# axiom_beta_interface_dummy.net
KiCad netlist of a schematic drawn in EAGLE
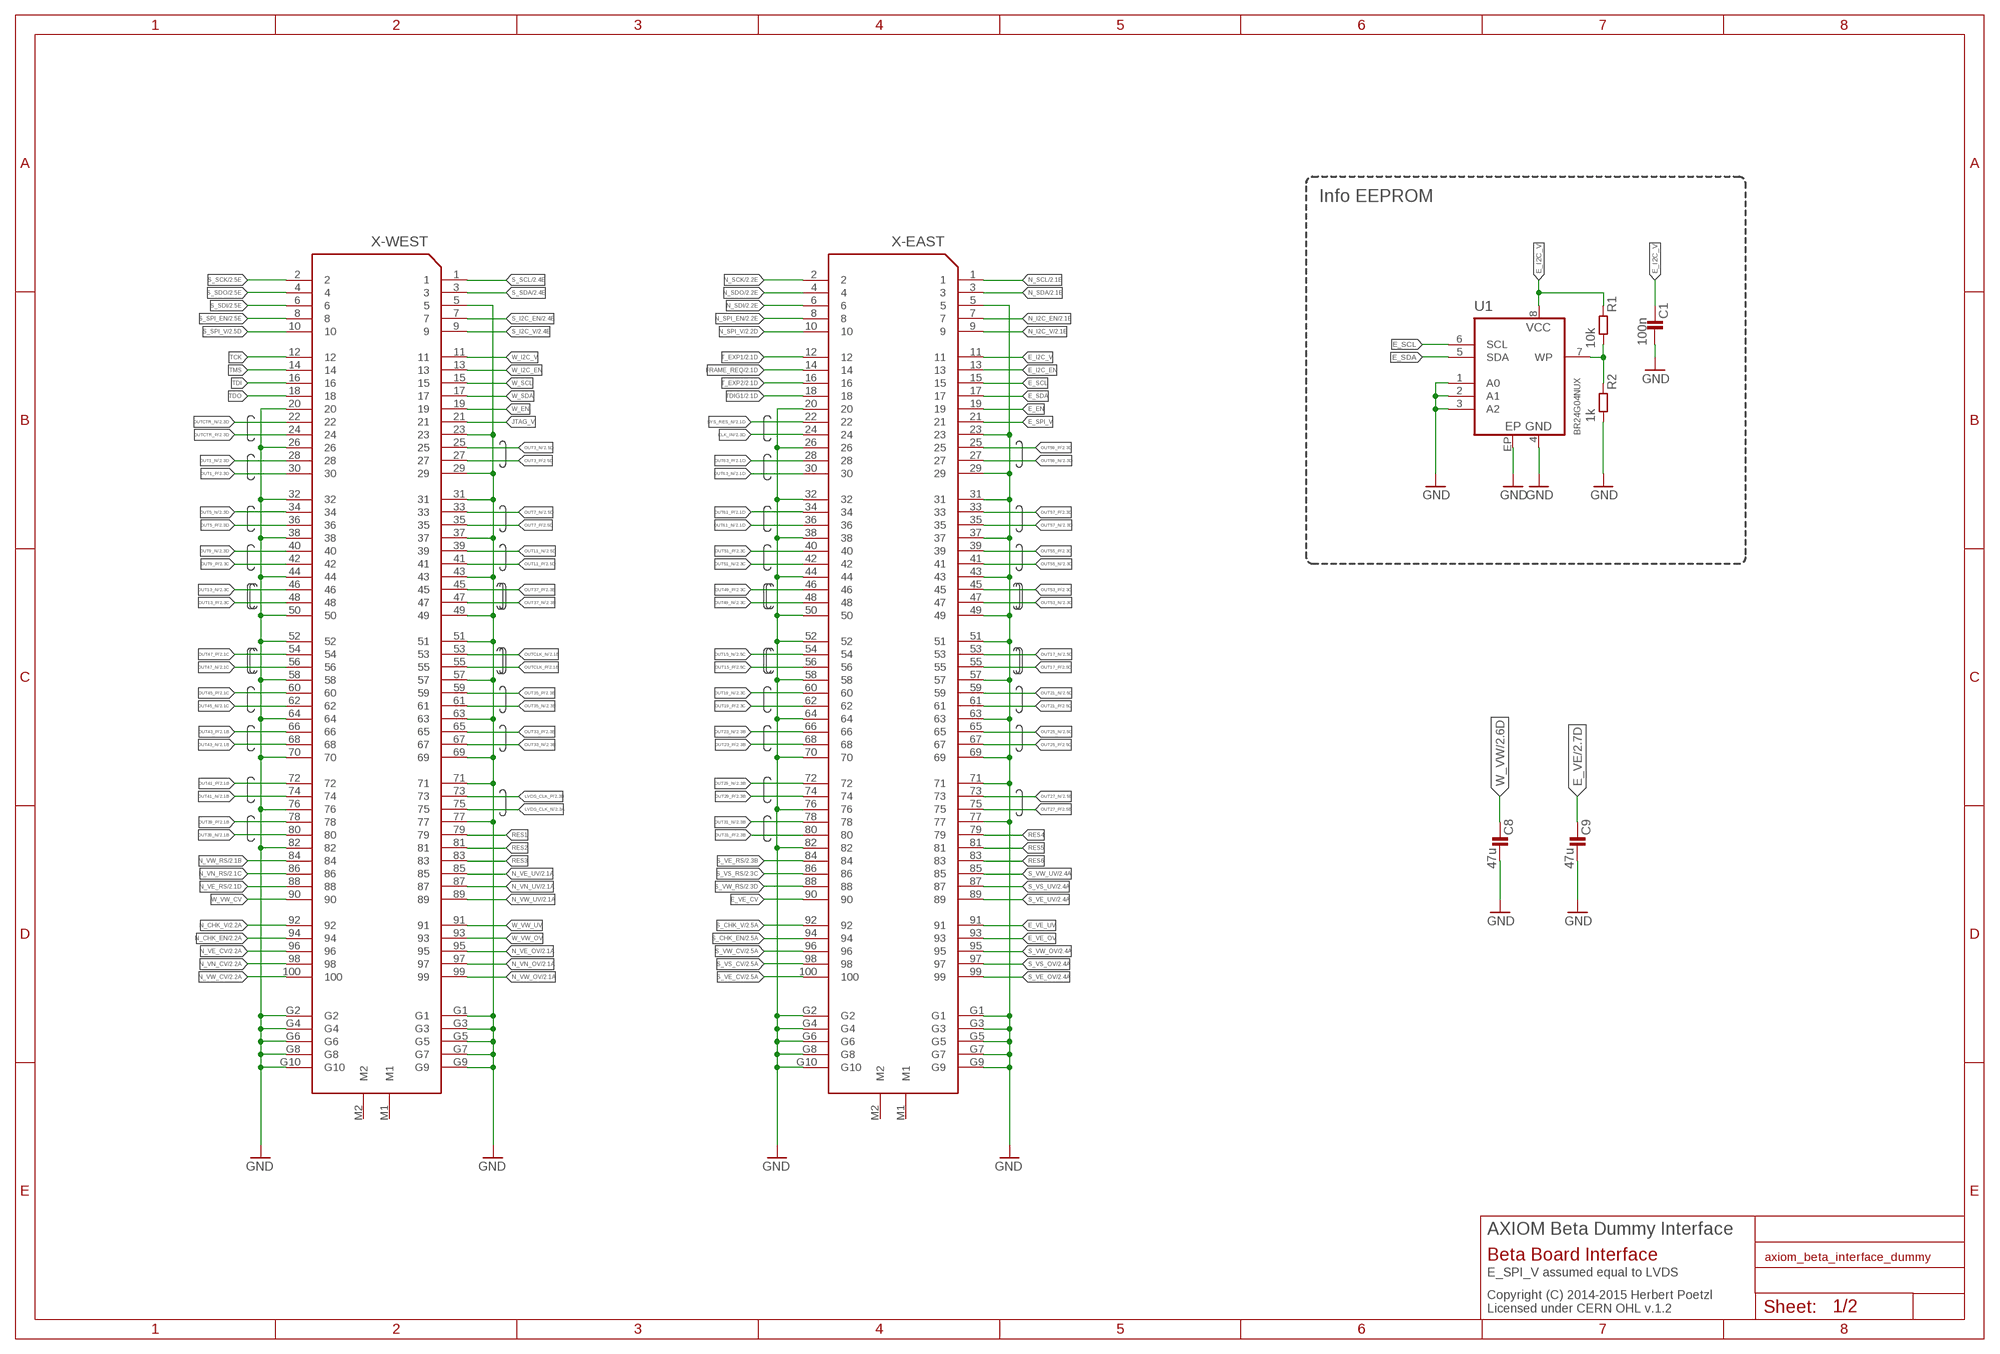
[diagram p0: schematic, sheet 1]
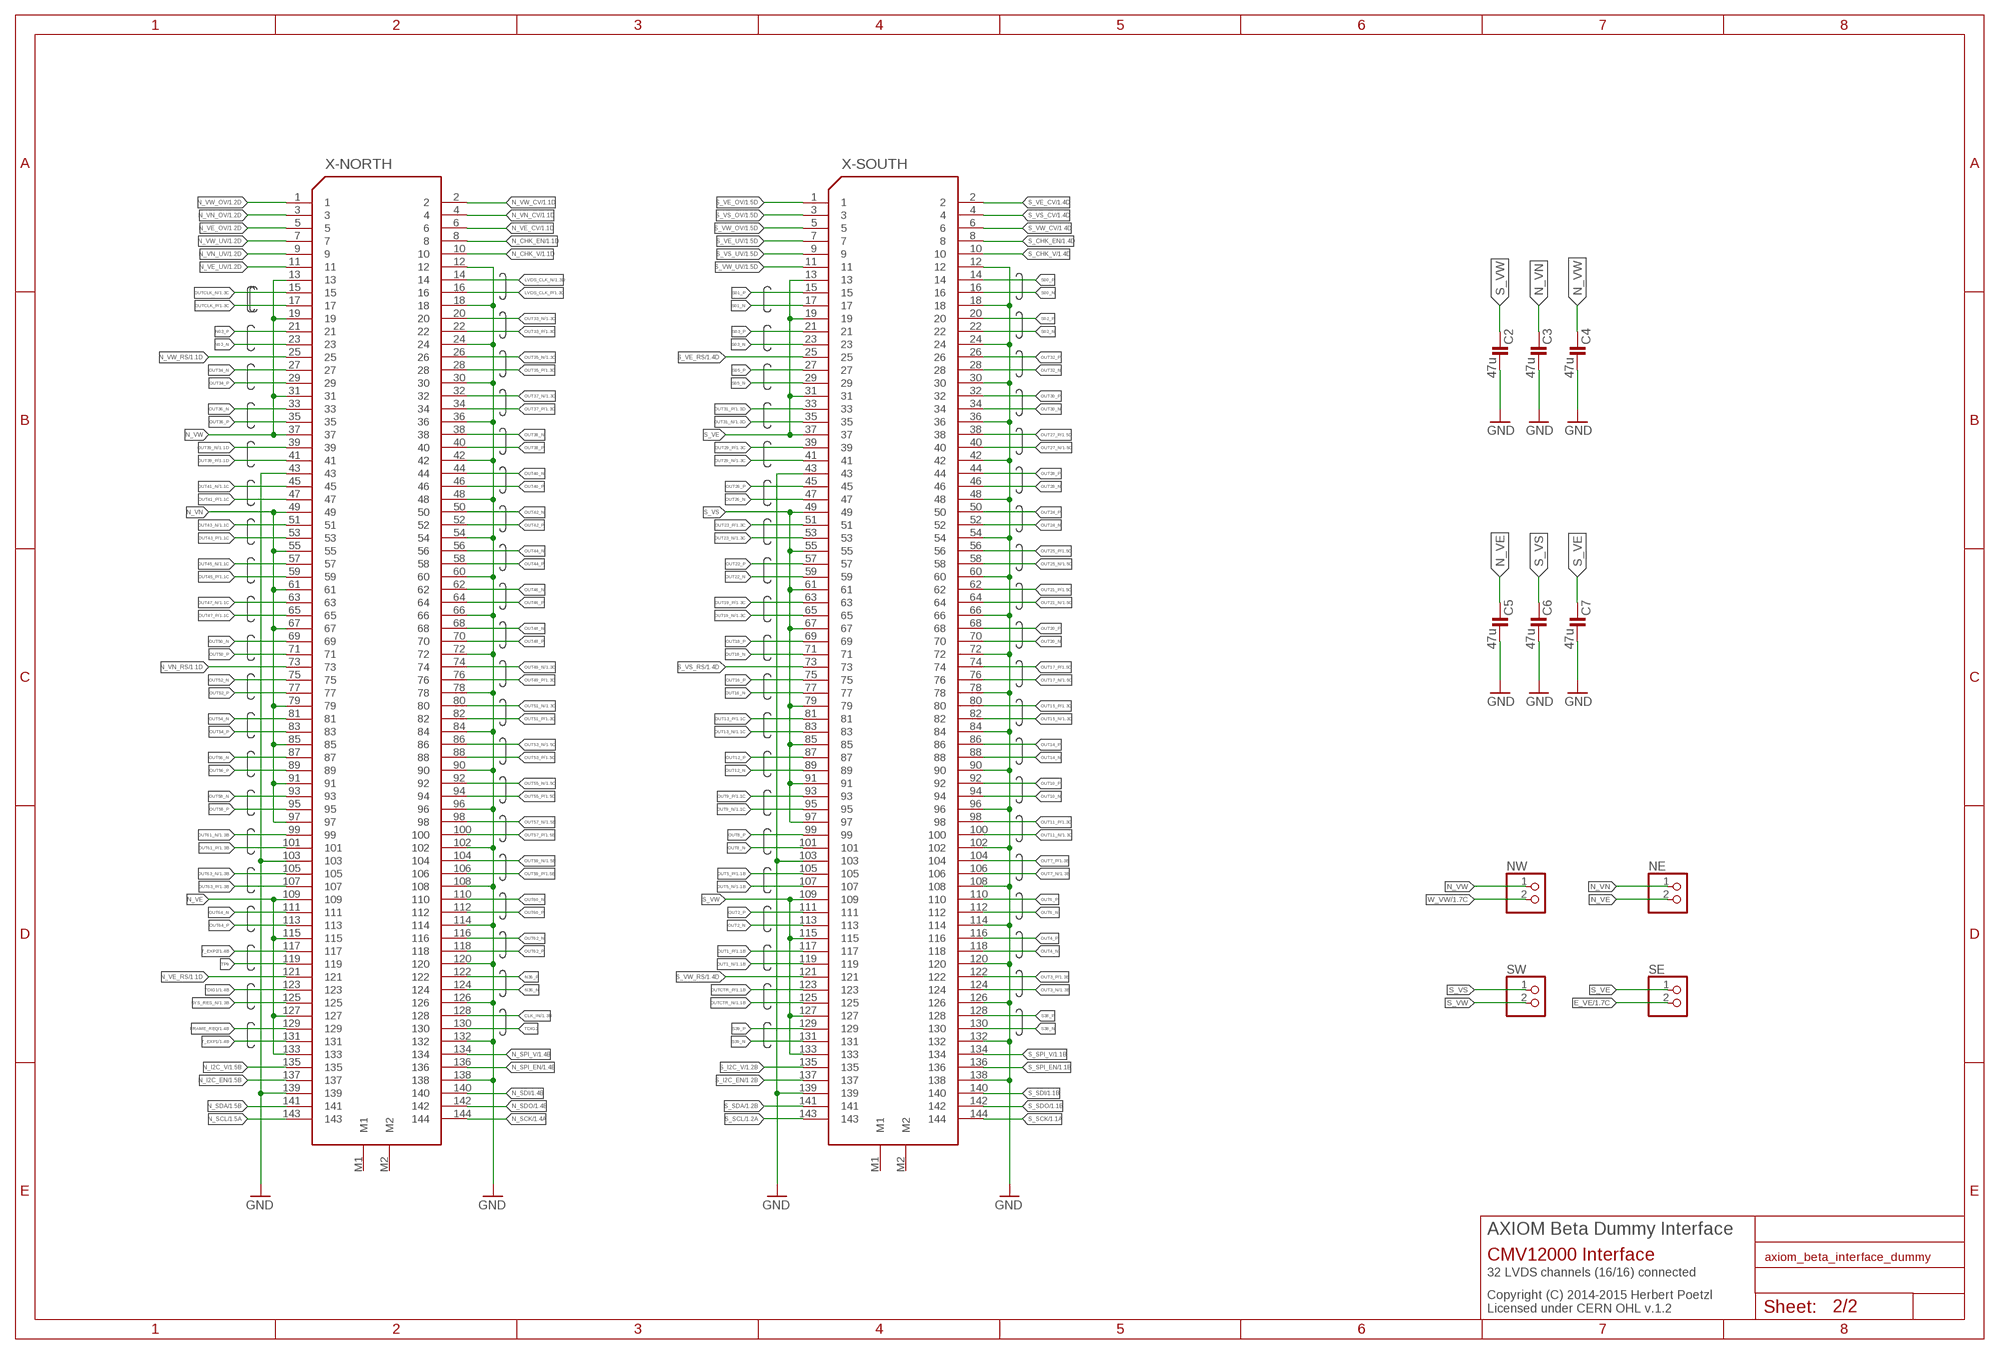
[diagram p1: schematic, sheet 2]

(export (version "E")
  (design (tool "Eeschema 10.0.6"))
  (components
    (comp (ref "C1")
      (value "100n")
      (footprint "eagle-import:0402-B")
      (libsource (lib "eagle-import") (part "C0402-B"))
    )
    (comp (ref "C8")
      (value "47u")
      (footprint "eagle-import:0805-B")
      (libsource (lib "eagle-import") (part "C0805-B"))
    )
    (comp (ref "C9")
      (value "47u")
      (footprint "eagle-import:0805-B")
      (libsource (lib "eagle-import") (part "C0805-B"))
    )
    (comp (ref "R1")
      (value "10k")
      (footprint "eagle-import:0402-B")
      (libsource (lib "eagle-import") (part "R0402-B"))
    )
    (comp (ref "R2")
      (value "1k")
      (footprint "eagle-import:0402-B")
      (libsource (lib "eagle-import") (part "R0402-B"))
    )
    (comp (ref "U1")
      (value "BR24G04NUX")
      (footprint "eagle-import:DFN200X300X100-9N")
      (libsource (lib "eagle-import") (part "BR24G04NUX"))
    )
    (comp (ref "X-EAST")
      (value "FX10-100/10P")
      (footprint "eagle-import:FX10A-100P_10")
      (libsource (lib "eagle-import") (part "FX10-100/10P"))
    )
    (comp (ref "X-WEST")
      (value "FX10-100/10P")
      (footprint "eagle-import:FX10A-100P_10")
      (libsource (lib "eagle-import") (part "FX10-100/10P"))
    )
    (comp (ref "C2")
      (value "47u")
      (footprint "eagle-import:0805-B")
      (libsource (lib "eagle-import") (part "C0805-B"))
    )
    (comp (ref "C3")
      (value "47u")
      (footprint "eagle-import:0805-B")
      (libsource (lib "eagle-import") (part "C0805-B"))
    )
    (comp (ref "C4")
      (value "47u")
      (footprint "eagle-import:0805-B")
      (libsource (lib "eagle-import") (part "C0805-B"))
    )
    (comp (ref "C5")
      (value "47u")
      (footprint "eagle-import:0805-B")
      (libsource (lib "eagle-import") (part "C0805-B"))
    )
    (comp (ref "C6")
      (value "47u")
      (footprint "eagle-import:0805-B")
      (libsource (lib "eagle-import") (part "C0805-B"))
    )
    (comp (ref "C7")
      (value "47u")
      (footprint "eagle-import:0805-B")
      (libsource (lib "eagle-import") (part "C0805-B"))
    )
    (comp (ref "NE")
      (value "PINHD-1X02_2.54")
      (footprint "eagle-import:1X02")
      (libsource (lib "eagle-import") (part "PINHD-1X02_2.54"))
    )
    (comp (ref "NW")
      (value "PINHD-1X02_2.54")
      (footprint "eagle-import:1X02")
      (libsource (lib "eagle-import") (part "PINHD-1X02_2.54"))
    )
    (comp (ref "SE")
      (value "PINHD-1X02_2.54")
      (footprint "eagle-import:1X02")
      (libsource (lib "eagle-import") (part "PINHD-1X02_2.54"))
    )
    (comp (ref "SW")
      (value "PINHD-1X02_2.54")
      (footprint "eagle-import:1X02")
      (libsource (lib "eagle-import") (part "PINHD-1X02_2.54"))
    )
    (comp (ref "X-NORTH")
      (value "FX10-144S")
      (footprint "eagle-import:FX10A-144S")
      (libsource (lib "eagle-import") (part "FX10-144S"))
    )
    (comp (ref "X-SOUTH")
      (value "FX10-144S")
      (footprint "eagle-import:FX10A-144S")
      (libsource (lib "eagle-import") (part "FX10-144S"))
    )
  )
  (nets
    (net (code "1") (name "CLK_IN") (class "Default")
      (node (ref "X-EAST") (pin "24") (pinfunction "24_24") (pintype "bidirectional"))
      (node (ref "X-NORTH") (pin "128") (pinfunction "128_128") (pintype "bidirectional"))
    )
    (net (code "2") (name "E_EN") (class "Default")
      (node (ref "X-EAST") (pin "19") (pinfunction "19_19") (pintype "bidirectional"))
    )
    (net (code "3") (name "E_I2C_EN") (class "Default")
      (node (ref "X-EAST") (pin "13") (pinfunction "13_13") (pintype "bidirectional"))
    )
    (net (code "4") (name "E_I2C_V") (class "Default")
      (node (ref "C1") (pin "1") (pinfunction "1_1") (pintype "passive"))
      (node (ref "R1") (pin "1") (pinfunction "1_1") (pintype "passive"))
      (node (ref "U1") (pin "8") (pinfunction "VCC_8") (pintype "power_in"))
      (node (ref "X-EAST") (pin "11") (pinfunction "11_11") (pintype "bidirectional"))
    )
    (net (code "5") (name "E_SCL") (class "Default")
      (node (ref "U1") (pin "6") (pinfunction "SCL_6") (pintype "input"))
      (node (ref "X-EAST") (pin "15") (pinfunction "15_15") (pintype "bidirectional"))
    )
    (net (code "6") (name "E_SDA") (class "Default")
      (node (ref "U1") (pin "5") (pinfunction "SDA_5") (pintype "bidirectional"))
      (node (ref "X-EAST") (pin "17") (pinfunction "17_17") (pintype "bidirectional"))
    )
    (net (code "7") (name "E_SPI_V") (class "Default")
      (node (ref "X-EAST") (pin "21") (pinfunction "21_21") (pintype "bidirectional"))
    )
    (net (code "8") (name "E_VE") (class "Default")
      (node (ref "C9") (pin "1") (pinfunction "1_1") (pintype "passive"))
      (node (ref "SE") (pin "2") (pinfunction "2_2") (pintype "passive"))
    )
    (net (code "9") (name "E_VE_CV") (class "Default")
      (node (ref "X-EAST") (pin "90") (pinfunction "90_90") (pintype "bidirectional"))
    )
    (net (code "10") (name "E_VE_OV") (class "Default")
      (node (ref "X-EAST") (pin "93") (pinfunction "93_93") (pintype "bidirectional"))
    )
    (net (code "11") (name "E_VE_UV") (class "Default")
      (node (ref "X-EAST") (pin "91") (pinfunction "91_91") (pintype "bidirectional"))
    )
    (net (code "12") (name "FRAME_REQ") (class "Default")
      (node (ref "X-EAST") (pin "14") (pinfunction "14_14") (pintype "bidirectional"))
      (node (ref "X-NORTH") (pin "129") (pinfunction "129_129") (pintype "bidirectional"))
    )
    (net (code "13") (name "GND") (class "Default")
      (node (ref "C1") (pin "2") (pinfunction "2_2") (pintype "passive"))
      (node (ref "C2") (pin "2") (pinfunction "2_2") (pintype "passive"))
      (node (ref "C3") (pin "2") (pinfunction "2_2") (pintype "passive"))
      (node (ref "C4") (pin "2") (pinfunction "2_2") (pintype "passive"))
      (node (ref "C5") (pin "2") (pinfunction "2_2") (pintype "passive"))
      (node (ref "C6") (pin "2") (pinfunction "2_2") (pintype "passive"))
      (node (ref "C7") (pin "2") (pinfunction "2_2") (pintype "passive"))
      (node (ref "C8") (pin "2") (pinfunction "2_2") (pintype "passive"))
      (node (ref "C9") (pin "2") (pinfunction "2_2") (pintype "passive"))
      (node (ref "R2") (pin "2") (pinfunction "2_2") (pintype "passive"))
      (node (ref "U1") (pin "1") (pinfunction "A0_1") (pintype "input"))
      (node (ref "U1") (pin "2") (pinfunction "A1_2") (pintype "input"))
      (node (ref "U1") (pin "3") (pinfunction "A2_3") (pintype "input"))
      (node (ref "U1") (pin "4") (pinfunction "GND_4") (pintype "passive"))
      (node (ref "U1") (pin "EP") (pinfunction "EP_EP") (pintype "passive"))
      (node (ref "X-EAST") (pin "20") (pinfunction "20_20") (pintype "bidirectional"))
      (node (ref "X-EAST") (pin "23") (pinfunction "23_23") (pintype "bidirectional"))
      (node (ref "X-EAST") (pin "26") (pinfunction "26_26") (pintype "bidirectional"))
      (node (ref "X-EAST") (pin "29") (pinfunction "29_29") (pintype "bidirectional"))
      (node (ref "X-EAST") (pin "31") (pinfunction "31_31") (pintype "bidirectional"))
      (node (ref "X-EAST") (pin "32") (pinfunction "32_32") (pintype "bidirectional"))
      (node (ref "X-EAST") (pin "37") (pinfunction "37_37") (pintype "bidirectional"))
      (node (ref "X-EAST") (pin "38") (pinfunction "38_38") (pintype "bidirectional"))
      (node (ref "X-EAST") (pin "43") (pinfunction "43_43") (pintype "bidirectional"))
      (node (ref "X-EAST") (pin "44") (pinfunction "44_44") (pintype "bidirectional"))
      (node (ref "X-EAST") (pin "49") (pinfunction "49_49") (pintype "bidirectional"))
      (node (ref "X-EAST") (pin "5") (pinfunction "5_5") (pintype "bidirectional"))
      (node (ref "X-EAST") (pin "50") (pinfunction "50_50") (pintype "bidirectional"))
      (node (ref "X-EAST") (pin "51") (pinfunction "51_51") (pintype "bidirectional"))
      (node (ref "X-EAST") (pin "52") (pinfunction "52_52") (pintype "bidirectional"))
      (node (ref "X-EAST") (pin "57") (pinfunction "57_57") (pintype "bidirectional"))
      (node (ref "X-EAST") (pin "58") (pinfunction "58_58") (pintype "bidirectional"))
      (node (ref "X-EAST") (pin "63") (pinfunction "63_63") (pintype "bidirectional"))
      (node (ref "X-EAST") (pin "64") (pinfunction "64_64") (pintype "bidirectional"))
      (node (ref "X-EAST") (pin "69") (pinfunction "69_69") (pintype "bidirectional"))
      (node (ref "X-EAST") (pin "70") (pinfunction "70_70") (pintype "bidirectional"))
      (node (ref "X-EAST") (pin "71") (pinfunction "71_71") (pintype "bidirectional"))
      (node (ref "X-EAST") (pin "76") (pinfunction "76_76") (pintype "bidirectional"))
      (node (ref "X-EAST") (pin "77") (pinfunction "77_77") (pintype "bidirectional"))
      (node (ref "X-EAST") (pin "82") (pinfunction "82_82") (pintype "bidirectional"))
      (node (ref "X-EAST") (pin "G1") (pinfunction "G1_G1") (pintype "bidirectional"))
      (node (ref "X-EAST") (pin "G10") (pinfunction "G10_G10") (pintype "bidirectional"))
      (node (ref "X-EAST") (pin "G2") (pinfunction "G2_G2") (pintype "bidirectional"))
      (node (ref "X-EAST") (pin "G3") (pinfunction "G3_G3") (pintype "bidirectional"))
      (node (ref "X-EAST") (pin "G4") (pinfunction "G4_G4") (pintype "bidirectional"))
      (node (ref "X-EAST") (pin "G5") (pinfunction "G5_G5") (pintype "bidirectional"))
      (node (ref "X-EAST") (pin "G6") (pinfunction "G6_G6") (pintype "bidirectional"))
      (node (ref "X-EAST") (pin "G7") (pinfunction "G7_G7") (pintype "bidirectional"))
      (node (ref "X-EAST") (pin "G8") (pinfunction "G8_G8") (pintype "bidirectional"))
      (node (ref "X-EAST") (pin "G9") (pinfunction "G9_G9") (pintype "bidirectional"))
      (node (ref "X-NORTH") (pin "102") (pinfunction "102_102") (pintype "bidirectional"))
      (node (ref "X-NORTH") (pin "103") (pinfunction "103_103") (pintype "bidirectional"))
      (node (ref "X-NORTH") (pin "108") (pinfunction "108_108") (pintype "bidirectional"))
      (node (ref "X-NORTH") (pin "114") (pinfunction "114_114") (pintype "bidirectional"))
      (node (ref "X-NORTH") (pin "12") (pinfunction "12_12") (pintype "bidirectional"))
      (node (ref "X-NORTH") (pin "120") (pinfunction "120_120") (pintype "bidirectional"))
      (node (ref "X-NORTH") (pin "126") (pinfunction "126_126") (pintype "bidirectional"))
      (node (ref "X-NORTH") (pin "132") (pinfunction "132_132") (pintype "bidirectional"))
      (node (ref "X-NORTH") (pin "138") (pinfunction "138_138") (pintype "bidirectional"))
      (node (ref "X-NORTH") (pin "139") (pinfunction "139_139") (pintype "bidirectional"))
      (node (ref "X-NORTH") (pin "18") (pinfunction "18_18") (pintype "bidirectional"))
      (node (ref "X-NORTH") (pin "24") (pinfunction "24_24") (pintype "bidirectional"))
      (node (ref "X-NORTH") (pin "30") (pinfunction "30_30") (pintype "bidirectional"))
      (node (ref "X-NORTH") (pin "36") (pinfunction "36_36") (pintype "bidirectional"))
      (node (ref "X-NORTH") (pin "42") (pinfunction "42_42") (pintype "bidirectional"))
      (node (ref "X-NORTH") (pin "43") (pinfunction "43_43") (pintype "bidirectional"))
      (node (ref "X-NORTH") (pin "48") (pinfunction "48_48") (pintype "bidirectional"))
      (node (ref "X-NORTH") (pin "54") (pinfunction "54_54") (pintype "bidirectional"))
      (node (ref "X-NORTH") (pin "60") (pinfunction "60_60") (pintype "bidirectional"))
      (node (ref "X-NORTH") (pin "66") (pinfunction "66_66") (pintype "bidirectional"))
      (node (ref "X-NORTH") (pin "72") (pinfunction "72_72") (pintype "bidirectional"))
      (node (ref "X-NORTH") (pin "78") (pinfunction "78_78") (pintype "bidirectional"))
      (node (ref "X-NORTH") (pin "84") (pinfunction "84_84") (pintype "bidirectional"))
      (node (ref "X-NORTH") (pin "90") (pinfunction "90_90") (pintype "bidirectional"))
      (node (ref "X-NORTH") (pin "96") (pinfunction "96_96") (pintype "bidirectional"))
      (node (ref "X-SOUTH") (pin "102") (pinfunction "102_102") (pintype "bidirectional"))
      (node (ref "X-SOUTH") (pin "103") (pinfunction "103_103") (pintype "bidirectional"))
      (node (ref "X-SOUTH") (pin "108") (pinfunction "108_108") (pintype "bidirectional"))
      (node (ref "X-SOUTH") (pin "114") (pinfunction "114_114") (pintype "bidirectional"))
      (node (ref "X-SOUTH") (pin "12") (pinfunction "12_12") (pintype "bidirectional"))
      (node (ref "X-SOUTH") (pin "120") (pinfunction "120_120") (pintype "bidirectional"))
      (node (ref "X-SOUTH") (pin "126") (pinfunction "126_126") (pintype "bidirectional"))
      (node (ref "X-SOUTH") (pin "132") (pinfunction "132_132") (pintype "bidirectional"))
      (node (ref "X-SOUTH") (pin "138") (pinfunction "138_138") (pintype "bidirectional"))
      (node (ref "X-SOUTH") (pin "139") (pinfunction "139_139") (pintype "bidirectional"))
      (node (ref "X-SOUTH") (pin "18") (pinfunction "18_18") (pintype "bidirectional"))
      (node (ref "X-SOUTH") (pin "24") (pinfunction "24_24") (pintype "bidirectional"))
      (node (ref "X-SOUTH") (pin "30") (pinfunction "30_30") (pintype "bidirectional"))
      (node (ref "X-SOUTH") (pin "36") (pinfunction "36_36") (pintype "bidirectional"))
      (node (ref "X-SOUTH") (pin "42") (pinfunction "42_42") (pintype "bidirectional"))
      (node (ref "X-SOUTH") (pin "43") (pinfunction "43_43") (pintype "bidirectional"))
      (node (ref "X-SOUTH") (pin "48") (pinfunction "48_48") (pintype "bidirectional"))
      (node (ref "X-SOUTH") (pin "54") (pinfunction "54_54") (pintype "bidirectional"))
      (node (ref "X-SOUTH") (pin "60") (pinfunction "60_60") (pintype "bidirectional"))
      (node (ref "X-SOUTH") (pin "66") (pinfunction "66_66") (pintype "bidirectional"))
      (node (ref "X-SOUTH") (pin "72") (pinfunction "72_72") (pintype "bidirectional"))
      (node (ref "X-SOUTH") (pin "78") (pinfunction "78_78") (pintype "bidirectional"))
      (node (ref "X-SOUTH") (pin "84") (pinfunction "84_84") (pintype "bidirectional"))
      (node (ref "X-SOUTH") (pin "90") (pinfunction "90_90") (pintype "bidirectional"))
      (node (ref "X-SOUTH") (pin "96") (pinfunction "96_96") (pintype "bidirectional"))
      (node (ref "X-WEST") (pin "20") (pinfunction "20_20") (pintype "bidirectional"))
      (node (ref "X-WEST") (pin "23") (pinfunction "23_23") (pintype "bidirectional"))
      (node (ref "X-WEST") (pin "26") (pinfunction "26_26") (pintype "bidirectional"))
      (node (ref "X-WEST") (pin "29") (pinfunction "29_29") (pintype "bidirectional"))
      (node (ref "X-WEST") (pin "31") (pinfunction "31_31") (pintype "bidirectional"))
      (node (ref "X-WEST") (pin "32") (pinfunction "32_32") (pintype "bidirectional"))
      (node (ref "X-WEST") (pin "37") (pinfunction "37_37") (pintype "bidirectional"))
      (node (ref "X-WEST") (pin "38") (pinfunction "38_38") (pintype "bidirectional"))
      (node (ref "X-WEST") (pin "43") (pinfunction "43_43") (pintype "bidirectional"))
      (node (ref "X-WEST") (pin "44") (pinfunction "44_44") (pintype "bidirectional"))
      (node (ref "X-WEST") (pin "49") (pinfunction "49_49") (pintype "bidirectional"))
      (node (ref "X-WEST") (pin "5") (pinfunction "5_5") (pintype "bidirectional"))
      (node (ref "X-WEST") (pin "50") (pinfunction "50_50") (pintype "bidirectional"))
      (node (ref "X-WEST") (pin "51") (pinfunction "51_51") (pintype "bidirectional"))
      (node (ref "X-WEST") (pin "52") (pinfunction "52_52") (pintype "bidirectional"))
      (node (ref "X-WEST") (pin "57") (pinfunction "57_57") (pintype "bidirectional"))
      (node (ref "X-WEST") (pin "58") (pinfunction "58_58") (pintype "bidirectional"))
      (node (ref "X-WEST") (pin "63") (pinfunction "63_63") (pintype "bidirectional"))
      (node (ref "X-WEST") (pin "64") (pinfunction "64_64") (pintype "bidirectional"))
      (node (ref "X-WEST") (pin "69") (pinfunction "69_69") (pintype "bidirectional"))
      (node (ref "X-WEST") (pin "70") (pinfunction "70_70") (pintype "bidirectional"))
      (node (ref "X-WEST") (pin "71") (pinfunction "71_71") (pintype "bidirectional"))
      (node (ref "X-WEST") (pin "76") (pinfunction "76_76") (pintype "bidirectional"))
      (node (ref "X-WEST") (pin "77") (pinfunction "77_77") (pintype "bidirectional"))
      (node (ref "X-WEST") (pin "82") (pinfunction "82_82") (pintype "bidirectional"))
      (node (ref "X-WEST") (pin "G1") (pinfunction "G1_G1") (pintype "bidirectional"))
      (node (ref "X-WEST") (pin "G10") (pinfunction "G10_G10") (pintype "bidirectional"))
      (node (ref "X-WEST") (pin "G2") (pinfunction "G2_G2") (pintype "bidirectional"))
      (node (ref "X-WEST") (pin "G3") (pinfunction "G3_G3") (pintype "bidirectional"))
      (node (ref "X-WEST") (pin "G4") (pinfunction "G4_G4") (pintype "bidirectional"))
      (node (ref "X-WEST") (pin "G5") (pinfunction "G5_G5") (pintype "bidirectional"))
      (node (ref "X-WEST") (pin "G6") (pinfunction "G6_G6") (pintype "bidirectional"))
      (node (ref "X-WEST") (pin "G7") (pinfunction "G7_G7") (pintype "bidirectional"))
      (node (ref "X-WEST") (pin "G8") (pinfunction "G8_G8") (pintype "bidirectional"))
      (node (ref "X-WEST") (pin "G9") (pinfunction "G9_G9") (pintype "bidirectional"))
    )
    (net (code "14") (name "JTAG_V") (class "Default")
      (node (ref "X-WEST") (pin "21") (pinfunction "21_21") (pintype "bidirectional"))
    )
    (net (code "15") (name "LVDS_CLK_N") (class "Default")
      (node (ref "X-NORTH") (pin "14") (pinfunction "14_14") (pintype "bidirectional"))
      (node (ref "X-WEST") (pin "75") (pinfunction "75_75") (pintype "bidirectional"))
    )
    (net (code "16") (name "LVDS_CLK_P") (class "Default")
      (node (ref "X-NORTH") (pin "16") (pinfunction "16_16") (pintype "bidirectional"))
      (node (ref "X-WEST") (pin "73") (pinfunction "73_73") (pintype "bidirectional"))
    )
    (net (code "17") (name "N03_N") (class "Default")
      (node (ref "X-NORTH") (pin "23") (pinfunction "23_23") (pintype "bidirectional"))
    )
    (net (code "18") (name "N03_P") (class "Default")
      (node (ref "X-NORTH") (pin "21") (pinfunction "21_21") (pintype "bidirectional"))
    )
    (net (code "19") (name "N36_N") (class "Default")
      (node (ref "X-NORTH") (pin "124") (pinfunction "124_124") (pintype "bidirectional"))
    )
    (net (code "20") (name "N36_P") (class "Default")
      (node (ref "X-NORTH") (pin "122") (pinfunction "122_122") (pintype "bidirectional"))
    )
    (net (code "21") (name "N_CHK_EN") (class "Default")
      (node (ref "X-NORTH") (pin "8") (pinfunction "8_8") (pintype "bidirectional"))
      (node (ref "X-WEST") (pin "94") (pinfunction "94_94") (pintype "bidirectional"))
    )
    (net (code "22") (name "N_CHK_V") (class "Default")
      (node (ref "X-NORTH") (pin "10") (pinfunction "10_10") (pintype "bidirectional"))
      (node (ref "X-WEST") (pin "92") (pinfunction "92_92") (pintype "bidirectional"))
    )
    (net (code "23") (name "N_I2C_EN") (class "Default")
      (node (ref "X-EAST") (pin "7") (pinfunction "7_7") (pintype "bidirectional"))
      (node (ref "X-NORTH") (pin "137") (pinfunction "137_137") (pintype "bidirectional"))
    )
    (net (code "24") (name "N_I2C_V") (class "Default")
      (node (ref "X-EAST") (pin "9") (pinfunction "9_9") (pintype "bidirectional"))
      (node (ref "X-NORTH") (pin "135") (pinfunction "135_135") (pintype "bidirectional"))
    )
    (net (code "25") (name "N_SCK") (class "Default")
      (node (ref "X-EAST") (pin "2") (pinfunction "2_2") (pintype "bidirectional"))
      (node (ref "X-NORTH") (pin "144") (pinfunction "144_144") (pintype "bidirectional"))
    )
    (net (code "26") (name "N_SCL") (class "Default")
      (node (ref "X-EAST") (pin "1") (pinfunction "1_1") (pintype "bidirectional"))
      (node (ref "X-NORTH") (pin "143") (pinfunction "143_143") (pintype "bidirectional"))
    )
    (net (code "27") (name "N_SDA") (class "Default")
      (node (ref "X-EAST") (pin "3") (pinfunction "3_3") (pintype "bidirectional"))
      (node (ref "X-NORTH") (pin "141") (pinfunction "141_141") (pintype "bidirectional"))
    )
    (net (code "28") (name "N_SDI") (class "Default")
      (node (ref "X-EAST") (pin "6") (pinfunction "6_6") (pintype "bidirectional"))
      (node (ref "X-NORTH") (pin "140") (pinfunction "140_140") (pintype "bidirectional"))
    )
    (net (code "29") (name "N_SDO") (class "Default")
      (node (ref "X-EAST") (pin "4") (pinfunction "4_4") (pintype "bidirectional"))
      (node (ref "X-NORTH") (pin "142") (pinfunction "142_142") (pintype "bidirectional"))
    )
    (net (code "30") (name "N_SPI_EN") (class "Default")
      (node (ref "X-EAST") (pin "8") (pinfunction "8_8") (pintype "bidirectional"))
      (node (ref "X-NORTH") (pin "136") (pinfunction "136_136") (pintype "bidirectional"))
    )
    (net (code "31") (name "N_SPI_V") (class "Default")
      (node (ref "X-EAST") (pin "10") (pinfunction "10_10") (pintype "bidirectional"))
      (node (ref "X-NORTH") (pin "134") (pinfunction "134_134") (pintype "bidirectional"))
    )
    (net (code "32") (name "N_VE") (class "Default")
      (node (ref "C5") (pin "1") (pinfunction "1_1") (pintype "passive"))
      (node (ref "NE") (pin "2") (pinfunction "2_2") (pintype "passive"))
      (node (ref "X-NORTH") (pin "109") (pinfunction "109_109") (pintype "bidirectional"))
      (node (ref "X-NORTH") (pin "115") (pinfunction "115_115") (pintype "bidirectional"))
      (node (ref "X-NORTH") (pin "127") (pinfunction "127_127") (pintype "bidirectional"))
      (node (ref "X-NORTH") (pin "133") (pinfunction "133_133") (pintype "bidirectional"))
    )
    (net (code "33") (name "N_VE_CV") (class "Default")
      (node (ref "X-NORTH") (pin "6") (pinfunction "6_6") (pintype "bidirectional"))
      (node (ref "X-WEST") (pin "96") (pinfunction "96_96") (pintype "bidirectional"))
    )
    (net (code "34") (name "N_VE_OV") (class "Default")
      (node (ref "X-NORTH") (pin "5") (pinfunction "5_5") (pintype "bidirectional"))
      (node (ref "X-WEST") (pin "95") (pinfunction "95_95") (pintype "bidirectional"))
    )
    (net (code "35") (name "N_VE_RS") (class "Default")
      (node (ref "X-NORTH") (pin "121") (pinfunction "121_121") (pintype "bidirectional"))
      (node (ref "X-WEST") (pin "88") (pinfunction "88_88") (pintype "bidirectional"))
    )
    (net (code "36") (name "N_VE_UV") (class "Default")
      (node (ref "X-NORTH") (pin "11") (pinfunction "11_11") (pintype "bidirectional"))
      (node (ref "X-WEST") (pin "85") (pinfunction "85_85") (pintype "bidirectional"))
    )
    (net (code "37") (name "N_VN") (class "Default")
      (node (ref "C3") (pin "1") (pinfunction "1_1") (pintype "passive"))
      (node (ref "NE") (pin "1") (pinfunction "1_1") (pintype "passive"))
      (node (ref "X-NORTH") (pin "49") (pinfunction "49_49") (pintype "bidirectional"))
      (node (ref "X-NORTH") (pin "55") (pinfunction "55_55") (pintype "bidirectional"))
      (node (ref "X-NORTH") (pin "61") (pinfunction "61_61") (pintype "bidirectional"))
      (node (ref "X-NORTH") (pin "67") (pinfunction "67_67") (pintype "bidirectional"))
      (node (ref "X-NORTH") (pin "79") (pinfunction "79_79") (pintype "bidirectional"))
      (node (ref "X-NORTH") (pin "85") (pinfunction "85_85") (pintype "bidirectional"))
      (node (ref "X-NORTH") (pin "91") (pinfunction "91_91") (pintype "bidirectional"))
      (node (ref "X-NORTH") (pin "97") (pinfunction "97_97") (pintype "bidirectional"))
    )
    (net (code "38") (name "N_VN_CV") (class "Default")
      (node (ref "X-NORTH") (pin "4") (pinfunction "4_4") (pintype "bidirectional"))
      (node (ref "X-WEST") (pin "98") (pinfunction "98_98") (pintype "bidirectional"))
    )
    (net (code "39") (name "N_VN_OV") (class "Default")
      (node (ref "X-NORTH") (pin "3") (pinfunction "3_3") (pintype "bidirectional"))
      (node (ref "X-WEST") (pin "97") (pinfunction "97_97") (pintype "bidirectional"))
    )
    (net (code "40") (name "N_VN_RS") (class "Default")
      (node (ref "X-NORTH") (pin "73") (pinfunction "73_73") (pintype "bidirectional"))
      (node (ref "X-WEST") (pin "86") (pinfunction "86_86") (pintype "bidirectional"))
    )
    (net (code "41") (name "N_VN_UV") (class "Default")
      (node (ref "X-NORTH") (pin "9") (pinfunction "9_9") (pintype "bidirectional"))
      (node (ref "X-WEST") (pin "87") (pinfunction "87_87") (pintype "bidirectional"))
    )
    (net (code "42") (name "N_VW") (class "Default")
      (node (ref "C4") (pin "1") (pinfunction "1_1") (pintype "passive"))
      (node (ref "NW") (pin "1") (pinfunction "1_1") (pintype "passive"))
      (node (ref "X-NORTH") (pin "13") (pinfunction "13_13") (pintype "bidirectional"))
      (node (ref "X-NORTH") (pin "19") (pinfunction "19_19") (pintype "bidirectional"))
      (node (ref "X-NORTH") (pin "31") (pinfunction "31_31") (pintype "bidirectional"))
      (node (ref "X-NORTH") (pin "37") (pinfunction "37_37") (pintype "bidirectional"))
    )
    (net (code "43") (name "N_VW_CV") (class "Default")
      (node (ref "X-NORTH") (pin "2") (pinfunction "2_2") (pintype "bidirectional"))
      (node (ref "X-WEST") (pin "100") (pinfunction "100_100") (pintype "bidirectional"))
    )
    (net (code "44") (name "N_VW_OV") (class "Default")
      (node (ref "X-NORTH") (pin "1") (pinfunction "1_1") (pintype "bidirectional"))
      (node (ref "X-WEST") (pin "99") (pinfunction "99_99") (pintype "bidirectional"))
    )
    (net (code "45") (name "N_VW_RS") (class "Default")
      (node (ref "X-NORTH") (pin "25") (pinfunction "25_25") (pintype "bidirectional"))
      (node (ref "X-WEST") (pin "84") (pinfunction "84_84") (pintype "bidirectional"))
    )
    (net (code "46") (name "N_VW_UV") (class "Default")
      (node (ref "X-NORTH") (pin "7") (pinfunction "7_7") (pintype "bidirectional"))
      (node (ref "X-WEST") (pin "89") (pinfunction "89_89") (pintype "bidirectional"))
    )
    (net (code "47") (name "Net-(U1-WP)") (class "Default")
      (node (ref "R1") (pin "2") (pinfunction "2_2") (pintype "passive"))
      (node (ref "R2") (pin "1") (pinfunction "1_1") (pintype "passive"))
      (node (ref "U1") (pin "7") (pinfunction "WP_7") (pintype "input"))
    )
    (net (code "48") (name "OUT1_N") (class "Default")
      (node (ref "X-SOUTH") (pin "119") (pinfunction "119_119") (pintype "bidirectional"))
      (node (ref "X-WEST") (pin "28") (pinfunction "28_28") (pintype "bidirectional"))
    )
    (net (code "49") (name "OUT1_P") (class "Default")
      (node (ref "X-SOUTH") (pin "117") (pinfunction "117_117") (pintype "bidirectional"))
      (node (ref "X-WEST") (pin "30") (pinfunction "30_30") (pintype "bidirectional"))
    )
    (net (code "50") (name "OUT2_N") (class "Default")
      (node (ref "X-SOUTH") (pin "113") (pinfunction "113_113") (pintype "bidirectional"))
    )
    (net (code "51") (name "OUT2_P") (class "Default")
      (node (ref "X-SOUTH") (pin "111") (pinfunction "111_111") (pintype "bidirectional"))
    )
    (net (code "52") (name "OUT3_N") (class "Default")
      (node (ref "X-SOUTH") (pin "124") (pinfunction "124_124") (pintype "bidirectional"))
      (node (ref "X-WEST") (pin "25") (pinfunction "25_25") (pintype "bidirectional"))
    )
    (net (code "53") (name "OUT3_P") (class "Default")
      (node (ref "X-SOUTH") (pin "122") (pinfunction "122_122") (pintype "bidirectional"))
      (node (ref "X-WEST") (pin "27") (pinfunction "27_27") (pintype "bidirectional"))
    )
    (net (code "54") (name "OUT4_N") (class "Default")
      (node (ref "X-SOUTH") (pin "118") (pinfunction "118_118") (pintype "bidirectional"))
    )
    (net (code "55") (name "OUT4_P") (class "Default")
      (node (ref "X-SOUTH") (pin "116") (pinfunction "116_116") (pintype "bidirectional"))
    )
    (net (code "56") (name "OUT5_N") (class "Default")
      (node (ref "X-SOUTH") (pin "107") (pinfunction "107_107") (pintype "bidirectional"))
      (node (ref "X-WEST") (pin "34") (pinfunction "34_34") (pintype "bidirectional"))
    )
    (net (code "57") (name "OUT5_P") (class "Default")
      (node (ref "X-SOUTH") (pin "105") (pinfunction "105_105") (pintype "bidirectional"))
      (node (ref "X-WEST") (pin "36") (pinfunction "36_36") (pintype "bidirectional"))
    )
    (net (code "58") (name "OUT6_N") (class "Default")
      (node (ref "X-SOUTH") (pin "112") (pinfunction "112_112") (pintype "bidirectional"))
    )
    (net (code "59") (name "OUT6_P") (class "Default")
      (node (ref "X-SOUTH") (pin "110") (pinfunction "110_110") (pintype "bidirectional"))
    )
    (net (code "60") (name "OUT7_N") (class "Default")
      (node (ref "X-SOUTH") (pin "106") (pinfunction "106_106") (pintype "bidirectional"))
      (node (ref "X-WEST") (pin "33") (pinfunction "33_33") (pintype "bidirectional"))
    )
    (net (code "61") (name "OUT7_P") (class "Default")
      (node (ref "X-SOUTH") (pin "104") (pinfunction "104_104") (pintype "bidirectional"))
      (node (ref "X-WEST") (pin "35") (pinfunction "35_35") (pintype "bidirectional"))
    )
    (net (code "62") (name "OUT8_N") (class "Default")
      (node (ref "X-SOUTH") (pin "101") (pinfunction "101_101") (pintype "bidirectional"))
    )
    (net (code "63") (name "OUT8_P") (class "Default")
      (node (ref "X-SOUTH") (pin "99") (pinfunction "99_99") (pintype "bidirectional"))
    )
    (net (code "64") (name "OUT9_N") (class "Default")
      (node (ref "X-SOUTH") (pin "95") (pinfunction "95_95") (pintype "bidirectional"))
      (node (ref "X-WEST") (pin "40") (pinfunction "40_40") (pintype "bidirectional"))
    )
    (net (code "65") (name "OUT9_P") (class "Default")
      (node (ref "X-SOUTH") (pin "93") (pinfunction "93_93") (pintype "bidirectional"))
      (node (ref "X-WEST") (pin "42") (pinfunction "42_42") (pintype "bidirectional"))
    )
    (net (code "66") (name "OUT10_N") (class "Default")
      (node (ref "X-SOUTH") (pin "94") (pinfunction "94_94") (pintype "bidirectional"))
    )
    (net (code "67") (name "OUT10_P") (class "Default")
      (node (ref "X-SOUTH") (pin "92") (pinfunction "92_92") (pintype "bidirectional"))
    )
    (net (code "68") (name "OUT11_N") (class "Default")
      (node (ref "X-SOUTH") (pin "100") (pinfunction "100_100") (pintype "bidirectional"))
      (node (ref "X-WEST") (pin "39") (pinfunction "39_39") (pintype "bidirectional"))
    )
    (net (code "69") (name "OUT11_P") (class "Default")
      (node (ref "X-SOUTH") (pin "98") (pinfunction "98_98") (pintype "bidirectional"))
      (node (ref "X-WEST") (pin "41") (pinfunction "41_41") (pintype "bidirectional"))
    )
    (net (code "70") (name "OUT12_N") (class "Default")
      (node (ref "X-SOUTH") (pin "89") (pinfunction "89_89") (pintype "bidirectional"))
    )
    (net (code "71") (name "OUT12_P") (class "Default")
      (node (ref "X-SOUTH") (pin "87") (pinfunction "87_87") (pintype "bidirectional"))
    )
    (net (code "72") (name "OUT13_N") (class "Default")
      (node (ref "X-SOUTH") (pin "83") (pinfunction "83_83") (pintype "bidirectional"))
      (node (ref "X-WEST") (pin "46") (pinfunction "46_46") (pintype "bidirectional"))
    )
    (net (code "73") (name "OUT13_P") (class "Default")
      (node (ref "X-SOUTH") (pin "81") (pinfunction "81_81") (pintype "bidirectional"))
      (node (ref "X-WEST") (pin "48") (pinfunction "48_48") (pintype "bidirectional"))
    )
    (net (code "74") (name "OUT14_N") (class "Default")
      (node (ref "X-SOUTH") (pin "88") (pinfunction "88_88") (pintype "bidirectional"))
    )
    (net (code "75") (name "OUT14_P") (class "Default")
      (node (ref "X-SOUTH") (pin "86") (pinfunction "86_86") (pintype "bidirectional"))
    )
    (net (code "76") (name "OUT15_N") (class "Default")
      (node (ref "X-EAST") (pin "54") (pinfunction "54_54") (pintype "bidirectional"))
      (node (ref "X-SOUTH") (pin "82") (pinfunction "82_82") (pintype "bidirectional"))
    )
    (net (code "77") (name "OUT15_P") (class "Default")
      (node (ref "X-EAST") (pin "56") (pinfunction "56_56") (pintype "bidirectional"))
      (node (ref "X-SOUTH") (pin "80") (pinfunction "80_80") (pintype "bidirectional"))
    )
    (net (code "78") (name "OUT16_N") (class "Default")
      (node (ref "X-SOUTH") (pin "77") (pinfunction "77_77") (pintype "bidirectional"))
    )
    (net (code "79") (name "OUT16_P") (class "Default")
      (node (ref "X-SOUTH") (pin "75") (pinfunction "75_75") (pintype "bidirectional"))
    )
    (net (code "80") (name "OUT17_N") (class "Default")
      (node (ref "X-EAST") (pin "53") (pinfunction "53_53") (pintype "bidirectional"))
      (node (ref "X-SOUTH") (pin "76") (pinfunction "76_76") (pintype "bidirectional"))
    )
    (net (code "81") (name "OUT17_P") (class "Default")
      (node (ref "X-EAST") (pin "55") (pinfunction "55_55") (pintype "bidirectional"))
      (node (ref "X-SOUTH") (pin "74") (pinfunction "74_74") (pintype "bidirectional"))
    )
    (net (code "82") (name "OUT18_N") (class "Default")
      (node (ref "X-SOUTH") (pin "71") (pinfunction "71_71") (pintype "bidirectional"))
    )
    (net (code "83") (name "OUT18_P") (class "Default")
      (node (ref "X-SOUTH") (pin "69") (pinfunction "69_69") (pintype "bidirectional"))
    )
    (net (code "84") (name "OUT19_N") (class "Default")
      (node (ref "X-EAST") (pin "60") (pinfunction "60_60") (pintype "bidirectional"))
      (node (ref "X-SOUTH") (pin "65") (pinfunction "65_65") (pintype "bidirectional"))
    )
    (net (code "85") (name "OUT19_P") (class "Default")
      (node (ref "X-EAST") (pin "62") (pinfunction "62_62") (pintype "bidirectional"))
      (node (ref "X-SOUTH") (pin "63") (pinfunction "63_63") (pintype "bidirectional"))
    )
    (net (code "86") (name "OUT20_N") (class "Default")
      (node (ref "X-SOUTH") (pin "70") (pinfunction "70_70") (pintype "bidirectional"))
    )
    (net (code "87") (name "OUT20_P") (class "Default")
      (node (ref "X-SOUTH") (pin "68") (pinfunction "68_68") (pintype "bidirectional"))
    )
    (net (code "88") (name "OUT21_N") (class "Default")
      (node (ref "X-EAST") (pin "59") (pinfunction "59_59") (pintype "bidirectional"))
      (node (ref "X-SOUTH") (pin "64") (pinfunction "64_64") (pintype "bidirectional"))
    )
    (net (code "89") (name "OUT21_P") (class "Default")
      (node (ref "X-EAST") (pin "61") (pinfunction "61_61") (pintype "bidirectional"))
      (node (ref "X-SOUTH") (pin "62") (pinfunction "62_62") (pintype "bidirectional"))
    )
    (net (code "90") (name "OUT22_N") (class "Default")
      (node (ref "X-SOUTH") (pin "59") (pinfunction "59_59") (pintype "bidirectional"))
    )
    (net (code "91") (name "OUT22_P") (class "Default")
      (node (ref "X-SOUTH") (pin "57") (pinfunction "57_57") (pintype "bidirectional"))
    )
    (net (code "92") (name "OUT23_N") (class "Default")
      (node (ref "X-EAST") (pin "66") (pinfunction "66_66") (pintype "bidirectional"))
      (node (ref "X-SOUTH") (pin "53") (pinfunction "53_53") (pintype "bidirectional"))
    )
    (net (code "93") (name "OUT23_P") (class "Default")
      (node (ref "X-EAST") (pin "68") (pinfunction "68_68") (pintype "bidirectional"))
      (node (ref "X-SOUTH") (pin "51") (pinfunction "51_51") (pintype "bidirectional"))
    )
    (net (code "94") (name "OUT24_N") (class "Default")
      (node (ref "X-SOUTH") (pin "52") (pinfunction "52_52") (pintype "bidirectional"))
    )
    (net (code "95") (name "OUT24_P") (class "Default")
      (node (ref "X-SOUTH") (pin "50") (pinfunction "50_50") (pintype "bidirectional"))
    )
    (net (code "96") (name "OUT25_N") (class "Default")
      (node (ref "X-EAST") (pin "65") (pinfunction "65_65") (pintype "bidirectional"))
      (node (ref "X-SOUTH") (pin "58") (pinfunction "58_58") (pintype "bidirectional"))
    )
    (net (code "97") (name "OUT25_P") (class "Default")
      (node (ref "X-EAST") (pin "67") (pinfunction "67_67") (pintype "bidirectional"))
      (node (ref "X-SOUTH") (pin "56") (pinfunction "56_56") (pintype "bidirectional"))
    )
    (net (code "98") (name "OUT26_N") (class "Default")
      (node (ref "X-SOUTH") (pin "47") (pinfunction "47_47") (pintype "bidirectional"))
    )
    (net (code "99") (name "OUT26_P") (class "Default")
      (node (ref "X-SOUTH") (pin "45") (pinfunction "45_45") (pintype "bidirectional"))
    )
    (net (code "100") (name "OUT27_N") (class "Default")
      (node (ref "X-EAST") (pin "73") (pinfunction "73_73") (pintype "bidirectional"))
      (node (ref "X-SOUTH") (pin "40") (pinfunction "40_40") (pintype "bidirectional"))
    )
    (net (code "101") (name "OUT27_P") (class "Default")
      (node (ref "X-EAST") (pin "75") (pinfunction "75_75") (pintype "bidirectional"))
      (node (ref "X-SOUTH") (pin "38") (pinfunction "38_38") (pintype "bidirectional"))
    )
    (net (code "102") (name "OUT28_N") (class "Default")
      (node (ref "X-SOUTH") (pin "46") (pinfunction "46_46") (pintype "bidirectional"))
    )
    (net (code "103") (name "OUT28_P") (class "Default")
      (node (ref "X-SOUTH") (pin "44") (pinfunction "44_44") (pintype "bidirectional"))
    )
    (net (code "104") (name "OUT29_N") (class "Default")
      (node (ref "X-EAST") (pin "72") (pinfunction "72_72") (pintype "bidirectional"))
      (node (ref "X-SOUTH") (pin "41") (pinfunction "41_41") (pintype "bidirectional"))
    )
    (net (code "105") (name "OUT29_P") (class "Default")
      (node (ref "X-EAST") (pin "74") (pinfunction "74_74") (pintype "bidirectional"))
      (node (ref "X-SOUTH") (pin "39") (pinfunction "39_39") (pintype "bidirectional"))
    )
    (net (code "106") (name "OUT30_N") (class "Default")
      (node (ref "X-SOUTH") (pin "34") (pinfunction "34_34") (pintype "bidirectional"))
    )
    (net (code "107") (name "OUT30_P") (class "Default")
      (node (ref "X-SOUTH") (pin "32") (pinfunction "32_32") (pintype "bidirectional"))
    )
    (net (code "108") (name "OUT31_N") (class "Default")
      (node (ref "X-EAST") (pin "78") (pinfunction "78_78") (pintype "bidirectional"))
      (node (ref "X-SOUTH") (pin "35") (pinfunction "35_35") (pintype "bidirectional"))
    )
    (net (code "109") (name "OUT31_P") (class "Default")
      (node (ref "X-EAST") (pin "80") (pinfunction "80_80") (pintype "bidirectional"))
      (node (ref "X-SOUTH") (pin "33") (pinfunction "33_33") (pintype "bidirectional"))
    )
    (net (code "110") (name "OUT32_N") (class "Default")
      (node (ref "X-SOUTH") (pin "28") (pinfunction "28_28") (pintype "bidirectional"))
    )
    (net (code "111") (name "OUT32_P") (class "Default")
      (node (ref "X-SOUTH") (pin "26") (pinfunction "26_26") (pintype "bidirectional"))
    )
    (net (code "112") (name "OUT33_N") (class "Default")
      (node (ref "X-NORTH") (pin "20") (pinfunction "20_20") (pintype "bidirectional"))
      (node (ref "X-WEST") (pin "67") (pinfunction "67_67") (pintype "bidirectional"))
    )
    (net (code "113") (name "OUT33_P") (class "Default")
      (node (ref "X-NORTH") (pin "22") (pinfunction "22_22") (pintype "bidirectional"))
      (node (ref "X-WEST") (pin "65") (pinfunction "65_65") (pintype "bidirectional"))
    )
    (net (code "114") (name "OUT34_N") (class "Default")
      (node (ref "X-NORTH") (pin "27") (pinfunction "27_27") (pintype "bidirectional"))
    )
    (net (code "115") (name "OUT34_P") (class "Default")
      (node (ref "X-NORTH") (pin "29") (pinfunction "29_29") (pintype "bidirectional"))
    )
    (net (code "116") (name "OUT35_N") (class "Default")
      (node (ref "X-NORTH") (pin "26") (pinfunction "26_26") (pintype "bidirectional"))
      (node (ref "X-WEST") (pin "61") (pinfunction "61_61") (pintype "bidirectional"))
    )
    (net (code "117") (name "OUT35_P") (class "Default")
      (node (ref "X-NORTH") (pin "28") (pinfunction "28_28") (pintype "bidirectional"))
      (node (ref "X-WEST") (pin "59") (pinfunction "59_59") (pintype "bidirectional"))
    )
    (net (code "118") (name "OUT36_N") (class "Default")
      (node (ref "X-NORTH") (pin "33") (pinfunction "33_33") (pintype "bidirectional"))
    )
    (net (code "119") (name "OUT36_P") (class "Default")
      (node (ref "X-NORTH") (pin "35") (pinfunction "35_35") (pintype "bidirectional"))
    )
    (net (code "120") (name "OUT37_N") (class "Default")
      (node (ref "X-NORTH") (pin "32") (pinfunction "32_32") (pintype "bidirectional"))
      (node (ref "X-WEST") (pin "47") (pinfunction "47_47") (pintype "bidirectional"))
    )
    (net (code "121") (name "OUT37_P") (class "Default")
      (node (ref "X-NORTH") (pin "34") (pinfunction "34_34") (pintype "bidirectional"))
      (node (ref "X-WEST") (pin "45") (pinfunction "45_45") (pintype "bidirectional"))
    )
    (net (code "122") (name "OUT38_N") (class "Default")
      (node (ref "X-NORTH") (pin "38") (pinfunction "38_38") (pintype "bidirectional"))
    )
    (net (code "123") (name "OUT38_P") (class "Default")
      (node (ref "X-NORTH") (pin "40") (pinfunction "40_40") (pintype "bidirectional"))
    )
    (net (code "124") (name "OUT39_N") (class "Default")
      (node (ref "X-NORTH") (pin "39") (pinfunction "39_39") (pintype "bidirectional"))
      (node (ref "X-WEST") (pin "80") (pinfunction "80_80") (pintype "bidirectional"))
    )
    (net (code "125") (name "OUT39_P") (class "Default")
      (node (ref "X-NORTH") (pin "41") (pinfunction "41_41") (pintype "bidirectional"))
      (node (ref "X-WEST") (pin "78") (pinfunction "78_78") (pintype "bidirectional"))
    )
    (net (code "126") (name "OUT40_N") (class "Default")
      (node (ref "X-NORTH") (pin "44") (pinfunction "44_44") (pintype "bidirectional"))
    )
    (net (code "127") (name "OUT40_P") (class "Default")
      (node (ref "X-NORTH") (pin "46") (pinfunction "46_46") (pintype "bidirectional"))
    )
    (net (code "128") (name "OUT41_N") (class "Default")
      (node (ref "X-NORTH") (pin "45") (pinfunction "45_45") (pintype "bidirectional"))
      (node (ref "X-WEST") (pin "74") (pinfunction "74_74") (pintype "bidirectional"))
    )
    (net (code "129") (name "OUT41_P") (class "Default")
      (node (ref "X-NORTH") (pin "47") (pinfunction "47_47") (pintype "bidirectional"))
      (node (ref "X-WEST") (pin "72") (pinfunction "72_72") (pintype "bidirectional"))
    )
    (net (code "130") (name "OUT42_N") (class "Default")
      (node (ref "X-NORTH") (pin "50") (pinfunction "50_50") (pintype "bidirectional"))
    )
    (net (code "131") (name "OUT42_P") (class "Default")
      (node (ref "X-NORTH") (pin "52") (pinfunction "52_52") (pintype "bidirectional"))
    )
    (net (code "132") (name "OUT43_N") (class "Default")
      (node (ref "X-NORTH") (pin "51") (pinfunction "51_51") (pintype "bidirectional"))
      (node (ref "X-WEST") (pin "68") (pinfunction "68_68") (pintype "bidirectional"))
    )
    (net (code "133") (name "OUT43_P") (class "Default")
      (node (ref "X-NORTH") (pin "53") (pinfunction "53_53") (pintype "bidirectional"))
      (node (ref "X-WEST") (pin "66") (pinfunction "66_66") (pintype "bidirectional"))
    )
    (net (code "134") (name "OUT44_N") (class "Default")
      (node (ref "X-NORTH") (pin "56") (pinfunction "56_56") (pintype "bidirectional"))
    )
    (net (code "135") (name "OUT44_P") (class "Default")
      (node (ref "X-NORTH") (pin "58") (pinfunction "58_58") (pintype "bidirectional"))
    )
    (net (code "136") (name "OUT45_N") (class "Default")
      (node (ref "X-NORTH") (pin "57") (pinfunction "57_57") (pintype "bidirectional"))
      (node (ref "X-WEST") (pin "62") (pinfunction "62_62") (pintype "bidirectional"))
    )
    (net (code "137") (name "OUT45_P") (class "Default")
      (node (ref "X-NORTH") (pin "59") (pinfunction "59_59") (pintype "bidirectional"))
      (node (ref "X-WEST") (pin "60") (pinfunction "60_60") (pintype "bidirectional"))
    )
    (net (code "138") (name "OUT46_N") (class "Default")
      (node (ref "X-NORTH") (pin "62") (pinfunction "62_62") (pintype "bidirectional"))
    )
    (net (code "139") (name "OUT46_P") (class "Default")
      (node (ref "X-NORTH") (pin "64") (pinfunction "64_64") (pintype "bidirectional"))
    )
    (net (code "140") (name "OUT47_N") (class "Default")
      (node (ref "X-NORTH") (pin "63") (pinfunction "63_63") (pintype "bidirectional"))
      (node (ref "X-WEST") (pin "56") (pinfunction "56_56") (pintype "bidirectional"))
    )
    (net (code "141") (name "OUT47_P") (class "Default")
      (node (ref "X-NORTH") (pin "65") (pinfunction "65_65") (pintype "bidirectional"))
      (node (ref "X-WEST") (pin "54") (pinfunction "54_54") (pintype "bidirectional"))
    )
    (net (code "142") (name "OUT48_N") (class "Default")
      (node (ref "X-NORTH") (pin "68") (pinfunction "68_68") (pintype "bidirectional"))
    )
    (net (code "143") (name "OUT48_P") (class "Default")
      (node (ref "X-NORTH") (pin "70") (pinfunction "70_70") (pintype "bidirectional"))
    )
    (net (code "144") (name "OUT49_N") (class "Default")
      (node (ref "X-EAST") (pin "48") (pinfunction "48_48") (pintype "bidirectional"))
      (node (ref "X-NORTH") (pin "74") (pinfunction "74_74") (pintype "bidirectional"))
    )
    (net (code "145") (name "OUT49_P") (class "Default")
      (node (ref "X-EAST") (pin "46") (pinfunction "46_46") (pintype "bidirectional"))
      (node (ref "X-NORTH") (pin "76") (pinfunction "76_76") (pintype "bidirectional"))
    )
    (net (code "146") (name "OUT50_N") (class "Default")
      (node (ref "X-NORTH") (pin "69") (pinfunction "69_69") (pintype "bidirectional"))
    )
    (net (code "147") (name "OUT50_P") (class "Default")
      (node (ref "X-NORTH") (pin "71") (pinfunction "71_71") (pintype "bidirectional"))
    )
    (net (code "148") (name "OUT51_N") (class "Default")
      (node (ref "X-EAST") (pin "42") (pinfunction "42_42") (pintype "bidirectional"))
      (node (ref "X-NORTH") (pin "80") (pinfunction "80_80") (pintype "bidirectional"))
    )
    (net (code "149") (name "OUT51_P") (class "Default")
      (node (ref "X-EAST") (pin "40") (pinfunction "40_40") (pintype "bidirectional"))
      (node (ref "X-NORTH") (pin "82") (pinfunction "82_82") (pintype "bidirectional"))
    )
    (net (code "150") (name "OUT52_N") (class "Default")
      (node (ref "X-NORTH") (pin "75") (pinfunction "75_75") (pintype "bidirectional"))
    )
    (net (code "151") (name "OUT52_P") (class "Default")
      (node (ref "X-NORTH") (pin "77") (pinfunction "77_77") (pintype "bidirectional"))
    )
    (net (code "152") (name "OUT53_N") (class "Default")
      (node (ref "X-EAST") (pin "47") (pinfunction "47_47") (pintype "bidirectional"))
      (node (ref "X-NORTH") (pin "86") (pinfunction "86_86") (pintype "bidirectional"))
    )
    (net (code "153") (name "OUT53_P") (class "Default")
      (node (ref "X-EAST") (pin "45") (pinfunction "45_45") (pintype "bidirectional"))
      (node (ref "X-NORTH") (pin "88") (pinfunction "88_88") (pintype "bidirectional"))
    )
    (net (code "154") (name "OUT54_N") (class "Default")
      (node (ref "X-NORTH") (pin "81") (pinfunction "81_81") (pintype "bidirectional"))
    )
    (net (code "155") (name "OUT54_P") (class "Default")
      (node (ref "X-NORTH") (pin "83") (pinfunction "83_83") (pintype "bidirectional"))
    )
    (net (code "156") (name "OUT55_N") (class "Default")
      (node (ref "X-EAST") (pin "41") (pinfunction "41_41") (pintype "bidirectional"))
      (node (ref "X-NORTH") (pin "92") (pinfunction "92_92") (pintype "bidirectional"))
    )
    (net (code "157") (name "OUT55_P") (class "Default")
      (node (ref "X-EAST") (pin "39") (pinfunction "39_39") (pintype "bidirectional"))
      (node (ref "X-NORTH") (pin "94") (pinfunction "94_94") (pintype "bidirectional"))
    )
    (net (code "158") (name "OUT56_N") (class "Default")
      (node (ref "X-NORTH") (pin "87") (pinfunction "87_87") (pintype "bidirectional"))
    )
    (net (code "159") (name "OUT56_P") (class "Default")
      (node (ref "X-NORTH") (pin "89") (pinfunction "89_89") (pintype "bidirectional"))
    )
    (net (code "160") (name "OUT57_N") (class "Default")
      (node (ref "X-EAST") (pin "35") (pinfunction "35_35") (pintype "bidirectional"))
      (node (ref "X-NORTH") (pin "98") (pinfunction "98_98") (pintype "bidirectional"))
    )
    (net (code "161") (name "OUT57_P") (class "Default")
      (node (ref "X-EAST") (pin "33") (pinfunction "33_33") (pintype "bidirectional"))
      (node (ref "X-NORTH") (pin "100") (pinfunction "100_100") (pintype "bidirectional"))
    )
    (net (code "162") (name "OUT58_N") (class "Default")
      (node (ref "X-NORTH") (pin "93") (pinfunction "93_93") (pintype "bidirectional"))
    )
    (net (code "163") (name "OUT58_P") (class "Default")
      (node (ref "X-NORTH") (pin "95") (pinfunction "95_95") (pintype "bidirectional"))
    )
    (net (code "164") (name "OUT59_N") (class "Default")
      (node (ref "X-EAST") (pin "27") (pinfunction "27_27") (pintype "bidirectional"))
      (node (ref "X-NORTH") (pin "104") (pinfunction "104_104") (pintype "bidirectional"))
    )
    (net (code "165") (name "OUT59_P") (class "Default")
      (node (ref "X-EAST") (pin "25") (pinfunction "25_25") (pintype "bidirectional"))
      (node (ref "X-NORTH") (pin "106") (pinfunction "106_106") (pintype "bidirectional"))
    )
    (net (code "166") (name "OUT60_N") (class "Default")
      (node (ref "X-NORTH") (pin "110") (pinfunction "110_110") (pintype "bidirectional"))
    )
    (net (code "167") (name "OUT60_P") (class "Default")
      (node (ref "X-NORTH") (pin "112") (pinfunction "112_112") (pintype "bidirectional"))
    )
    (net (code "168") (name "OUT61_N") (class "Default")
      (node (ref "X-EAST") (pin "36") (pinfunction "36_36") (pintype "bidirectional"))
      (node (ref "X-NORTH") (pin "99") (pinfunction "99_99") (pintype "bidirectional"))
    )
    (net (code "169") (name "OUT61_P") (class "Default")
      (node (ref "X-EAST") (pin "34") (pinfunction "34_34") (pintype "bidirectional"))
      (node (ref "X-NORTH") (pin "101") (pinfunction "101_101") (pintype "bidirectional"))
    )
    (net (code "170") (name "OUT62_N") (class "Default")
      (node (ref "X-NORTH") (pin "116") (pinfunction "116_116") (pintype "bidirectional"))
    )
    (net (code "171") (name "OUT62_P") (class "Default")
      (node (ref "X-NORTH") (pin "118") (pinfunction "118_118") (pintype "bidirectional"))
    )
    (net (code "172") (name "OUT63_N") (class "Default")
      (node (ref "X-EAST") (pin "30") (pinfunction "30_30") (pintype "bidirectional"))
      (node (ref "X-NORTH") (pin "105") (pinfunction "105_105") (pintype "bidirectional"))
    )
    (net (code "173") (name "OUT63_P") (class "Default")
      (node (ref "X-EAST") (pin "28") (pinfunction "28_28") (pintype "bidirectional"))
      (node (ref "X-NORTH") (pin "107") (pinfunction "107_107") (pintype "bidirectional"))
    )
    (net (code "174") (name "OUT64_N") (class "Default")
      (node (ref "X-NORTH") (pin "111") (pinfunction "111_111") (pintype "bidirectional"))
    )
    (net (code "175") (name "OUT64_P") (class "Default")
      (node (ref "X-NORTH") (pin "113") (pinfunction "113_113") (pintype "bidirectional"))
    )
    (net (code "176") (name "OUTCLK_N") (class "Default")
      (node (ref "X-NORTH") (pin "15") (pinfunction "15_15") (pintype "bidirectional"))
      (node (ref "X-WEST") (pin "53") (pinfunction "53_53") (pintype "bidirectional"))
    )
    (net (code "177") (name "OUTCLK_P") (class "Default")
      (node (ref "X-NORTH") (pin "17") (pinfunction "17_17") (pintype "bidirectional"))
      (node (ref "X-WEST") (pin "55") (pinfunction "55_55") (pintype "bidirectional"))
    )
    (net (code "178") (name "OUTCTR_N") (class "Default")
      (node (ref "X-SOUTH") (pin "125") (pinfunction "125_125") (pintype "bidirectional"))
      (node (ref "X-WEST") (pin "22") (pinfunction "22_22") (pintype "bidirectional"))
    )
    (net (code "179") (name "OUTCTR_P") (class "Default")
      (node (ref "X-SOUTH") (pin "123") (pinfunction "123_123") (pintype "bidirectional"))
      (node (ref "X-WEST") (pin "24") (pinfunction "24_24") (pintype "bidirectional"))
    )
    (net (code "180") (name "RES1") (class "Default")
      (node (ref "X-WEST") (pin "79") (pinfunction "79_79") (pintype "bidirectional"))
    )
    (net (code "181") (name "RES2") (class "Default")
      (node (ref "X-WEST") (pin "81") (pinfunction "81_81") (pintype "bidirectional"))
    )
    (net (code "182") (name "RES3") (class "Default")
      (node (ref "X-WEST") (pin "83") (pinfunction "83_83") (pintype "bidirectional"))
    )
    (net (code "183") (name "RES4") (class "Default")
      (node (ref "X-EAST") (pin "79") (pinfunction "79_79") (pintype "bidirectional"))
    )
    (net (code "184") (name "RES5") (class "Default")
      (node (ref "X-EAST") (pin "81") (pinfunction "81_81") (pintype "bidirectional"))
    )
    (net (code "185") (name "RES6") (class "Default")
      (node (ref "X-EAST") (pin "83") (pinfunction "83_83") (pintype "bidirectional"))
    )
    (net (code "186") (name "S00_N") (class "Default")
      (node (ref "X-SOUTH") (pin "16") (pinfunction "16_16") (pintype "bidirectional"))
    )
    (net (code "187") (name "S00_P") (class "Default")
      (node (ref "X-SOUTH") (pin "14") (pinfunction "14_14") (pintype "bidirectional"))
    )
    (net (code "188") (name "S01_N") (class "Default")
      (node (ref "X-SOUTH") (pin "17") (pinfunction "17_17") (pintype "bidirectional"))
    )
    (net (code "189") (name "S01_P") (class "Default")
      (node (ref "X-SOUTH") (pin "15") (pinfunction "15_15") (pintype "bidirectional"))
    )
    (net (code "190") (name "S02_N") (class "Default")
      (node (ref "X-SOUTH") (pin "22") (pinfunction "22_22") (pintype "bidirectional"))
    )
    (net (code "191") (name "S02_P") (class "Default")
      (node (ref "X-SOUTH") (pin "20") (pinfunction "20_20") (pintype "bidirectional"))
    )
    (net (code "192") (name "S03_N") (class "Default")
      (node (ref "X-SOUTH") (pin "23") (pinfunction "23_23") (pintype "bidirectional"))
    )
    (net (code "193") (name "S03_P") (class "Default")
      (node (ref "X-SOUTH") (pin "21") (pinfunction "21_21") (pintype "bidirectional"))
    )
    (net (code "194") (name "S05_N") (class "Default")
      (node (ref "X-SOUTH") (pin "29") (pinfunction "29_29") (pintype "bidirectional"))
    )
    (net (code "195") (name "S05_P") (class "Default")
      (node (ref "X-SOUTH") (pin "27") (pinfunction "27_27") (pintype "bidirectional"))
    )
    (net (code "196") (name "S38_N") (class "Default")
      (node (ref "X-SOUTH") (pin "130") (pinfunction "130_130") (pintype "bidirectional"))
    )
    (net (code "197") (name "S38_P") (class "Default")
      (node (ref "X-SOUTH") (pin "128") (pinfunction "128_128") (pintype "bidirectional"))
    )
    (net (code "198") (name "S39_N") (class "Default")
      (node (ref "X-SOUTH") (pin "131") (pinfunction "131_131") (pintype "bidirectional"))
    )
    (net (code "199") (name "S39_P") (class "Default")
      (node (ref "X-SOUTH") (pin "129") (pinfunction "129_129") (pintype "bidirectional"))
    )
    (net (code "200") (name "SYS_RES_N") (class "Default")
      (node (ref "X-EAST") (pin "22") (pinfunction "22_22") (pintype "bidirectional"))
      (node (ref "X-NORTH") (pin "125") (pinfunction "125_125") (pintype "bidirectional"))
    )
    (net (code "201") (name "S_CHK_EN") (class "Default")
      (node (ref "X-EAST") (pin "94") (pinfunction "94_94") (pintype "bidirectional"))
      (node (ref "X-SOUTH") (pin "8") (pinfunction "8_8") (pintype "bidirectional"))
    )
    (net (code "202") (name "S_CHK_V") (class "Default")
      (node (ref "X-EAST") (pin "92") (pinfunction "92_92") (pintype "bidirectional"))
      (node (ref "X-SOUTH") (pin "10") (pinfunction "10_10") (pintype "bidirectional"))
    )
    (net (code "203") (name "S_I2C_EN") (class "Default")
      (node (ref "X-SOUTH") (pin "137") (pinfunction "137_137") (pintype "bidirectional"))
      (node (ref "X-WEST") (pin "7") (pinfunction "7_7") (pintype "bidirectional"))
    )
    (net (code "204") (name "S_I2C_V") (class "Default")
      (node (ref "X-SOUTH") (pin "135") (pinfunction "135_135") (pintype "bidirectional"))
      (node (ref "X-WEST") (pin "9") (pinfunction "9_9") (pintype "bidirectional"))
    )
    (net (code "205") (name "S_SCK") (class "Default")
      (node (ref "X-SOUTH") (pin "144") (pinfunction "144_144") (pintype "bidirectional"))
      (node (ref "X-WEST") (pin "2") (pinfunction "2_2") (pintype "bidirectional"))
    )
    (net (code "206") (name "S_SCL") (class "Default")
      (node (ref "X-SOUTH") (pin "143") (pinfunction "143_143") (pintype "bidirectional"))
      (node (ref "X-WEST") (pin "1") (pinfunction "1_1") (pintype "bidirectional"))
    )
    (net (code "207") (name "S_SDA") (class "Default")
      (node (ref "X-SOUTH") (pin "141") (pinfunction "141_141") (pintype "bidirectional"))
      (node (ref "X-WEST") (pin "3") (pinfunction "3_3") (pintype "bidirectional"))
    )
    (net (code "208") (name "S_SDI") (class "Default")
      (node (ref "X-SOUTH") (pin "140") (pinfunction "140_140") (pintype "bidirectional"))
      (node (ref "X-WEST") (pin "6") (pinfunction "6_6") (pintype "bidirectional"))
    )
    (net (code "209") (name "S_SDO") (class "Default")
      (node (ref "X-SOUTH") (pin "142") (pinfunction "142_142") (pintype "bidirectional"))
      (node (ref "X-WEST") (pin "4") (pinfunction "4_4") (pintype "bidirectional"))
    )
    (net (code "210") (name "S_SPI_EN") (class "Default")
      (node (ref "X-SOUTH") (pin "136") (pinfunction "136_136") (pintype "bidirectional"))
      (node (ref "X-WEST") (pin "8") (pinfunction "8_8") (pintype "bidirectional"))
    )
    (net (code "211") (name "S_SPI_V") (class "Default")
      (node (ref "X-SOUTH") (pin "134") (pinfunction "134_134") (pintype "bidirectional"))
      (node (ref "X-WEST") (pin "10") (pinfunction "10_10") (pintype "bidirectional"))
    )
    (net (code "212") (name "S_VE") (class "Default")
      (node (ref "C7") (pin "1") (pinfunction "1_1") (pintype "passive"))
      (node (ref "SE") (pin "1") (pinfunction "1_1") (pintype "passive"))
      (node (ref "X-SOUTH") (pin "13") (pinfunction "13_13") (pintype "bidirectional"))
      (node (ref "X-SOUTH") (pin "19") (pinfunction "19_19") (pintype "bidirectional"))
      (node (ref "X-SOUTH") (pin "31") (pinfunction "31_31") (pintype "bidirectional"))
      (node (ref "X-SOUTH") (pin "37") (pinfunction "37_37") (pintype "bidirectional"))
    )
    (net (code "213") (name "S_VE_CV") (class "Default")
      (node (ref "X-EAST") (pin "100") (pinfunction "100_100") (pintype "bidirectional"))
      (node (ref "X-SOUTH") (pin "2") (pinfunction "2_2") (pintype "bidirectional"))
    )
    (net (code "214") (name "S_VE_OV") (class "Default")
      (node (ref "X-EAST") (pin "99") (pinfunction "99_99") (pintype "bidirectional"))
      (node (ref "X-SOUTH") (pin "1") (pinfunction "1_1") (pintype "bidirectional"))
    )
    (net (code "215") (name "S_VE_RS") (class "Default")
      (node (ref "X-EAST") (pin "84") (pinfunction "84_84") (pintype "bidirectional"))
      (node (ref "X-SOUTH") (pin "25") (pinfunction "25_25") (pintype "bidirectional"))
    )
    (net (code "216") (name "S_VE_UV") (class "Default")
      (node (ref "X-EAST") (pin "89") (pinfunction "89_89") (pintype "bidirectional"))
      (node (ref "X-SOUTH") (pin "7") (pinfunction "7_7") (pintype "bidirectional"))
    )
    (net (code "217") (name "S_VS") (class "Default")
      (node (ref "C6") (pin "1") (pinfunction "1_1") (pintype "passive"))
      (node (ref "SW") (pin "1") (pinfunction "1_1") (pintype "passive"))
      (node (ref "X-SOUTH") (pin "49") (pinfunction "49_49") (pintype "bidirectional"))
      (node (ref "X-SOUTH") (pin "55") (pinfunction "55_55") (pintype "bidirectional"))
      (node (ref "X-SOUTH") (pin "61") (pinfunction "61_61") (pintype "bidirectional"))
      (node (ref "X-SOUTH") (pin "67") (pinfunction "67_67") (pintype "bidirectional"))
      (node (ref "X-SOUTH") (pin "79") (pinfunction "79_79") (pintype "bidirectional"))
      (node (ref "X-SOUTH") (pin "85") (pinfunction "85_85") (pintype "bidirectional"))
      (node (ref "X-SOUTH") (pin "91") (pinfunction "91_91") (pintype "bidirectional"))
      (node (ref "X-SOUTH") (pin "97") (pinfunction "97_97") (pintype "bidirectional"))
    )
    (net (code "218") (name "S_VS_CV") (class "Default")
      (node (ref "X-EAST") (pin "98") (pinfunction "98_98") (pintype "bidirectional"))
      (node (ref "X-SOUTH") (pin "4") (pinfunction "4_4") (pintype "bidirectional"))
    )
    (net (code "219") (name "S_VS_OV") (class "Default")
      (node (ref "X-EAST") (pin "97") (pinfunction "97_97") (pintype "bidirectional"))
      (node (ref "X-SOUTH") (pin "3") (pinfunction "3_3") (pintype "bidirectional"))
    )
    (net (code "220") (name "S_VS_RS") (class "Default")
      (node (ref "X-EAST") (pin "86") (pinfunction "86_86") (pintype "bidirectional"))
      (node (ref "X-SOUTH") (pin "73") (pinfunction "73_73") (pintype "bidirectional"))
    )
    (net (code "221") (name "S_VS_UV") (class "Default")
      (node (ref "X-EAST") (pin "87") (pinfunction "87_87") (pintype "bidirectional"))
      (node (ref "X-SOUTH") (pin "9") (pinfunction "9_9") (pintype "bidirectional"))
    )
    (net (code "222") (name "S_VW") (class "Default")
      (node (ref "C2") (pin "1") (pinfunction "1_1") (pintype "passive"))
      (node (ref "SW") (pin "2") (pinfunction "2_2") (pintype "passive"))
      (node (ref "X-SOUTH") (pin "109") (pinfunction "109_109") (pintype "bidirectional"))
      (node (ref "X-SOUTH") (pin "115") (pinfunction "115_115") (pintype "bidirectional"))
      (node (ref "X-SOUTH") (pin "127") (pinfunction "127_127") (pintype "bidirectional"))
      (node (ref "X-SOUTH") (pin "133") (pinfunction "133_133") (pintype "bidirectional"))
    )
    (net (code "223") (name "S_VW_CV") (class "Default")
      (node (ref "X-EAST") (pin "96") (pinfunction "96_96") (pintype "bidirectional"))
      (node (ref "X-SOUTH") (pin "6") (pinfunction "6_6") (pintype "bidirectional"))
    )
    (net (code "224") (name "S_VW_OV") (class "Default")
      (node (ref "X-EAST") (pin "95") (pinfunction "95_95") (pintype "bidirectional"))
      (node (ref "X-SOUTH") (pin "5") (pinfunction "5_5") (pintype "bidirectional"))
    )
    (net (code "225") (name "S_VW_RS") (class "Default")
      (node (ref "X-EAST") (pin "88") (pinfunction "88_88") (pintype "bidirectional"))
      (node (ref "X-SOUTH") (pin "121") (pinfunction "121_121") (pintype "bidirectional"))
    )
    (net (code "226") (name "S_VW_UV") (class "Default")
      (node (ref "X-EAST") (pin "85") (pinfunction "85_85") (pintype "bidirectional"))
      (node (ref "X-SOUTH") (pin "11") (pinfunction "11_11") (pintype "bidirectional"))
    )
    (net (code "227") (name "TCK") (class "Default")
      (node (ref "X-WEST") (pin "12") (pinfunction "12_12") (pintype "bidirectional"))
    )
    (net (code "228") (name "TDI") (class "Default")
      (node (ref "X-WEST") (pin "16") (pinfunction "16_16") (pintype "bidirectional"))
    )
    (net (code "229") (name "TDIG1") (class "Default")
      (node (ref "X-EAST") (pin "18") (pinfunction "18_18") (pintype "bidirectional"))
      (node (ref "X-NORTH") (pin "123") (pinfunction "123_123") (pintype "bidirectional"))
    )
    (net (code "230") (name "TDIG2") (class "Default")
      (node (ref "X-NORTH") (pin "130") (pinfunction "130_130") (pintype "bidirectional"))
    )
    (net (code "231") (name "TDO") (class "Default")
      (node (ref "X-WEST") (pin "18") (pinfunction "18_18") (pintype "bidirectional"))
    )
    (net (code "232") (name "TMS") (class "Default")
      (node (ref "X-WEST") (pin "14") (pinfunction "14_14") (pintype "bidirectional"))
    )
    (net (code "233") (name "TP9") (class "Default")
      (node (ref "X-NORTH") (pin "119") (pinfunction "119_119") (pintype "bidirectional"))
    )
    (net (code "234") (name "T_EXP1") (class "Default")
      (node (ref "X-EAST") (pin "12") (pinfunction "12_12") (pintype "bidirectional"))
      (node (ref "X-NORTH") (pin "131") (pinfunction "131_131") (pintype "bidirectional"))
    )
    (net (code "235") (name "T_EXP2") (class "Default")
      (node (ref "X-EAST") (pin "16") (pinfunction "16_16") (pintype "bidirectional"))
      (node (ref "X-NORTH") (pin "117") (pinfunction "117_117") (pintype "bidirectional"))
    )
    (net (code "236") (name "W_EN") (class "Default")
      (node (ref "X-WEST") (pin "19") (pinfunction "19_19") (pintype "bidirectional"))
    )
    (net (code "237") (name "W_I2C_EN") (class "Default")
      (node (ref "X-WEST") (pin "13") (pinfunction "13_13") (pintype "bidirectional"))
    )
    (net (code "238") (name "W_I2C_V") (class "Default")
      (node (ref "X-WEST") (pin "11") (pinfunction "11_11") (pintype "bidirectional"))
    )
    (net (code "239") (name "W_SCL") (class "Default")
      (node (ref "X-WEST") (pin "15") (pinfunction "15_15") (pintype "bidirectional"))
    )
    (net (code "240") (name "W_SDA") (class "Default")
      (node (ref "X-WEST") (pin "17") (pinfunction "17_17") (pintype "bidirectional"))
    )
    (net (code "241") (name "W_VW") (class "Default")
      (node (ref "C8") (pin "1") (pinfunction "1_1") (pintype "passive"))
      (node (ref "NW") (pin "2") (pinfunction "2_2") (pintype "passive"))
    )
    (net (code "242") (name "W_VW_CV") (class "Default")
      (node (ref "X-WEST") (pin "90") (pinfunction "90_90") (pintype "bidirectional"))
    )
    (net (code "243") (name "W_VW_OV") (class "Default")
      (node (ref "X-WEST") (pin "93") (pinfunction "93_93") (pintype "bidirectional"))
    )
    (net (code "244") (name "W_VW_UV") (class "Default")
      (node (ref "X-WEST") (pin "91") (pinfunction "91_91") (pintype "bidirectional"))
    )
    (net (code "245") (name "unconnected-(X-EAST-PadM1)") (class "Default")
      (node (ref "X-EAST") (pin "M1") (pinfunction "M1_M1") (pintype "bidirectional"))
    )
    (net (code "246") (name "unconnected-(X-EAST-PadM2)") (class "Default")
      (node (ref "X-EAST") (pin "M2") (pinfunction "M2_M2") (pintype "bidirectional"))
    )
    (net (code "247") (name "unconnected-(X-NORTH-PadM1)") (class "Default")
      (node (ref "X-NORTH") (pin "M1") (pinfunction "M1_M1") (pintype "bidirectional"))
    )
    (net (code "248") (name "unconnected-(X-NORTH-PadM2)") (class "Default")
      (node (ref "X-NORTH") (pin "M2") (pinfunction "M2_M2") (pintype "bidirectional"))
    )
    (net (code "249") (name "unconnected-(X-SOUTH-PadM1)") (class "Default")
      (node (ref "X-SOUTH") (pin "M1") (pinfunction "M1_M1") (pintype "bidirectional"))
    )
    (net (code "250") (name "unconnected-(X-SOUTH-PadM2)") (class "Default")
      (node (ref "X-SOUTH") (pin "M2") (pinfunction "M2_M2") (pintype "bidirectional"))
    )
    (net (code "251") (name "unconnected-(X-WEST-PadM1)") (class "Default")
      (node (ref "X-WEST") (pin "M1") (pinfunction "M1_M1") (pintype "bidirectional"))
    )
    (net (code "252") (name "unconnected-(X-WEST-PadM2)") (class "Default")
      (node (ref "X-WEST") (pin "M2") (pinfunction "M2_M2") (pintype "bidirectional"))
    )
  )
)
